# design.net
KiCad netlist of a schematic drawn in Altium Designer
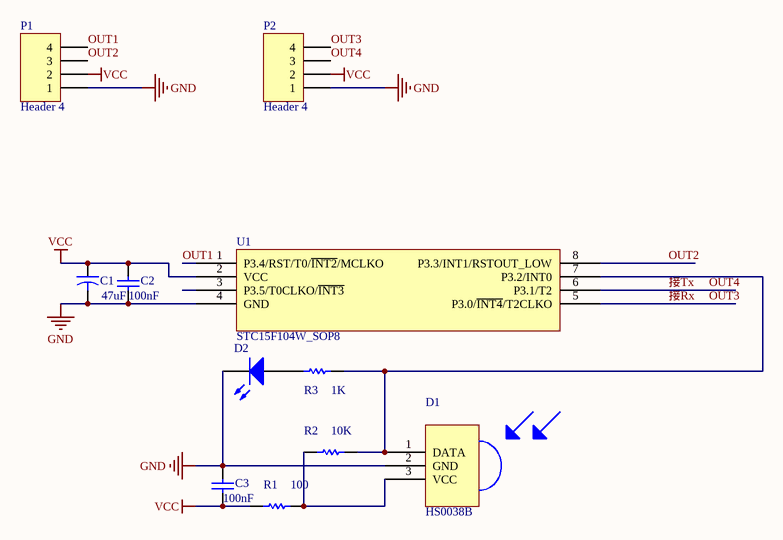
[diagram p0: 红外接收电路.SchDoc]

(export (version "E")
  (design (tool "Eeschema 10.0.6"))
  (components
    (comp (ref "C1")
      (value "47uF")
      (footprint "C1210_N")
      (description "Capacitor")
      (fields (field (name "Comment") "Cap2") (field (name "PUBLISHER") "Altium Limited"))
      (libsource (lib "Miscellaneous Devices") (part "Cap2"))
    )
    (comp (ref "C2")
      (value "100nF")
      (footprint "6-0805_N")
      (description "Capacitor")
      (fields (field (name "Comment") "Cap") (field (name "PUBLISHER") "Altium Limited"))
      (libsource (lib "Miscellaneous Devices") (part "Cap"))
    )
    (comp (ref "C3")
      (value "100nF")
      (footprint "6-0805_N")
      (description "Capacitor")
      (fields (field (name "Comment") "Cap") (field (name "PUBLISHER") "Altium Limited"))
      (libsource (lib "Miscellaneous Devices") (part "Cap"))
    )
    (comp (ref "D1") (value "HS0038B") (footprint "E3") (libsource (lib "Lib") (part "HS0038B")))
    (comp (ref "D2")
      (value "LED1")
      (footprint "6-0805_N")
      (description "Typical RED GaAs LED")
      (fields (field (name "PUBLISHER") "Altium Limited"))
      (libsource (lib "Miscellaneous Devices") (part "LED1"))
    )
    (comp (ref "P1")
      (value "Header 4")
      (footprint "HDR1X4")
      (description "Header, 4-Pin")
      (fields (field (name "PUBLISHER") "Altium Limited"))
      (libsource (lib "Miscellaneous Connectors") (part "Header 4"))
    )
    (comp (ref "P2")
      (value "Header 4")
      (footprint "HDR1X4")
      (description "Header, 4-Pin")
      (fields (field (name "PUBLISHER") "Altium Limited"))
      (libsource (lib "Miscellaneous Connectors") (part "Header 4"))
    )
    (comp (ref "R1")
      (value "100")
      (footprint "6-0805_N")
      (description "Resistor")
      (fields (field (name "Comment") "Res1") (field (name "PUBLISHER") "Altium Limited"))
      (libsource (lib "Miscellaneous Devices") (part "Res1"))
    )
    (comp (ref "R2")
      (value "10K")
      (footprint "6-0805_N")
      (description "Resistor")
      (fields (field (name "Comment") "Res1") (field (name "PUBLISHER") "Altium Limited"))
      (libsource (lib "Miscellaneous Devices") (part "Res1"))
    )
    (comp (ref "R3")
      (value "1K")
      (footprint "6-0805_N")
      (description "Resistor")
      (fields (field (name "Comment") "Res1") (field (name "PUBLISHER") "Altium Limited"))
      (libsource (lib "Miscellaneous Devices") (part "Res1"))
    )
    (comp (ref "U1")
      (value "STC15F104W_SOP8")
      (footprint "DFN8")
      (libsource (lib "stcmcu_altium_lib") (part "STC15F101W_SOP8_DIP8"))
    )
  )
  (nets
    (net (code "1") (name "/OUT1") (class "Default")
      (node (ref "P1") (pin "4") (pinfunction "4_4") (pintype "passive"))
      (node (ref "U1") (pin "1") (pinfunction "P3.4/RST/T0/~{INT2}/MCLKO_1") (pintype "passive"))
    )
    (net (code "2") (name "/OUT2") (class "Default")
      (node (ref "P1") (pin "3") (pinfunction "3_3") (pintype "passive"))
      (node (ref "U1") (pin "8") (pinfunction "P3.3/INT1/RSTOUT_LOW_8") (pintype "passive"))
    )
    (net (code "3") (name "/OUT3") (class "Default")
      (node (ref "P2") (pin "4") (pinfunction "4_4") (pintype "passive"))
      (node (ref "U1") (pin "5") (pinfunction "P3.0/~{INT4}/T2CLKO_5") (pintype "passive"))
    )
    (net (code "4") (name "/OUT4") (class "Default")
      (node (ref "P2") (pin "3") (pinfunction "3_3") (pintype "passive"))
      (node (ref "U1") (pin "6") (pinfunction "P3.1/T2_6") (pintype "passive"))
    )
    (net (code "5") (name "GND") (class "Default")
      (node (ref "C1") (pin "2") (pinfunction "2_2") (pintype "passive"))
      (node (ref "C2") (pin "1") (pinfunction "1_1") (pintype "passive"))
      (node (ref "C3") (pin "2") (pinfunction "2_2") (pintype "passive"))
      (node (ref "D1") (pin "2") (pinfunction "GND_2") (pintype "passive"))
      (node (ref "D2") (pin "2") (pinfunction "K_2") (pintype "passive"))
      (node (ref "P1") (pin "1") (pinfunction "1_1") (pintype "passive"))
      (node (ref "P2") (pin "1") (pinfunction "1_1") (pintype "passive"))
      (node (ref "U1") (pin "4") (pinfunction "GND_4") (pintype "passive"))
    )
    (net (code "6") (name "Net-(D1-DATA)") (class "Default")
      (node (ref "D1") (pin "1") (pinfunction "DATA_1") (pintype "passive"))
      (node (ref "R2") (pin "2") (pinfunction "2_2") (pintype "passive"))
      (node (ref "R3") (pin "2") (pinfunction "2_2") (pintype "passive"))
      (node (ref "U1") (pin "7") (pinfunction "P3.2/INT0_7") (pintype "passive"))
    )
    (net (code "7") (name "Net-(D1-VCC)") (class "Default")
      (node (ref "D1") (pin "3") (pinfunction "VCC_3") (pintype "passive"))
      (node (ref "R1") (pin "2") (pinfunction "2_2") (pintype "passive"))
      (node (ref "R2") (pin "1") (pinfunction "1_1") (pintype "passive"))
    )
    (net (code "8") (name "Net-(D2-A)") (class "Default")
      (node (ref "D2") (pin "1") (pinfunction "A_1") (pintype "passive"))
      (node (ref "R3") (pin "1") (pinfunction "1_1") (pintype "passive"))
    )
    (net (code "9") (name "VCC") (class "Default")
      (node (ref "C1") (pin "1") (pinfunction "1_1") (pintype "passive"))
      (node (ref "C2") (pin "2") (pinfunction "2_2") (pintype "passive"))
      (node (ref "C3") (pin "1") (pinfunction "1_1") (pintype "passive"))
      (node (ref "P1") (pin "2") (pinfunction "2_2") (pintype "passive"))
      (node (ref "P2") (pin "2") (pinfunction "2_2") (pintype "passive"))
      (node (ref "R1") (pin "1") (pinfunction "1_1") (pintype "passive"))
      (node (ref "U1") (pin "2") (pinfunction "VCC_2") (pintype "passive"))
    )
    (net (code "10") (name "unconnected-(U1-P3.5{slash}T0CLKO{slash}~{INT3}-Pad3)") (class "Default")
      (node (ref "U1") (pin "3") (pinfunction "P3.5/T0CLKO/~{INT3}_3") (pintype "passive"))
    )
  )
)
